# MCU.net
KiCad netlist of a schematic drawn in Altium Designer
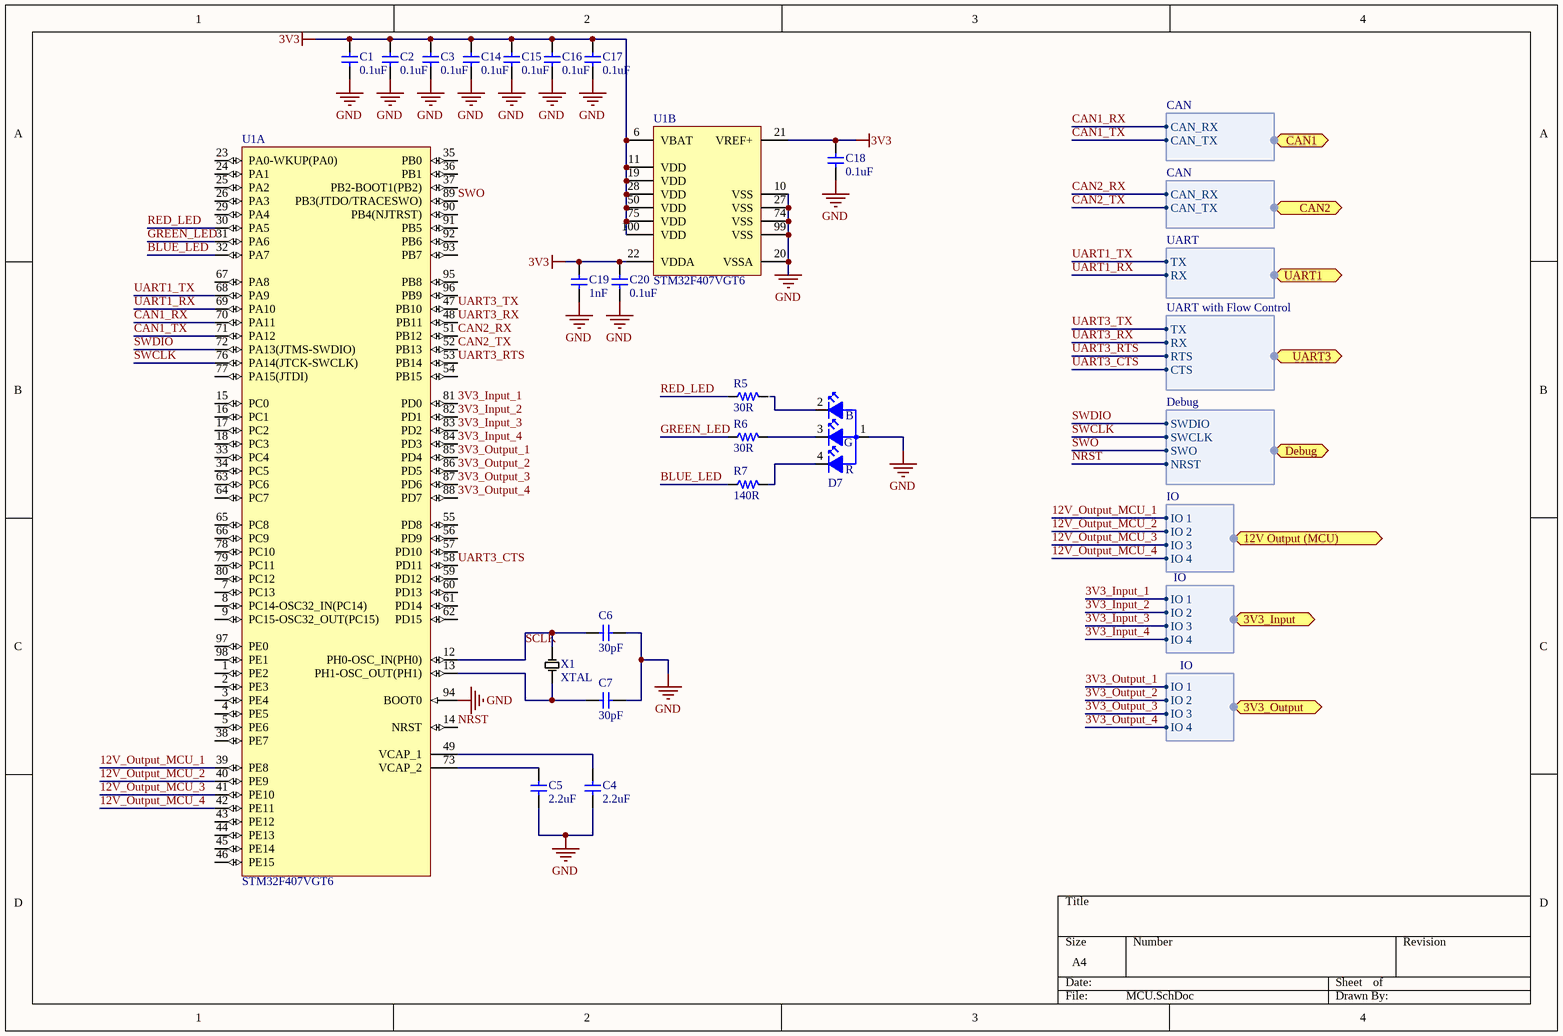
[diagram p0: MCU.SchDoc]

(export (version "E")
  (design (tool "Eeschema 10.0.6"))
  (components
    (comp (ref "C1")
      (value "0.1uF")
      (footprint "PCB_GENERIC_SMD_0603")
      (description "CAP CER 0603 0.1uF 16V X5R 20%")
      (fields (field (name "TOLERANCE") "20%") (field (name "VOLTAGE") "16V"))
      (libsource (lib "CAP-0603") (part "C060-000U1-00"))
    )
    (comp (ref "C2")
      (value "0.1uF")
      (footprint "PCB_GENERIC_SMD_0603")
      (description "CAP CER 0603 0.1uF 16V X5R 20%")
      (fields (field (name "TOLERANCE") "20%") (field (name "VOLTAGE") "16V"))
      (libsource (lib "CAP-0603") (part "C060-000U1-00"))
    )
    (comp (ref "C3")
      (value "0.1uF")
      (footprint "PCB_GENERIC_SMD_0603")
      (description "CAP CER 0603 0.1uF 16V X5R 20%")
      (fields (field (name "TOLERANCE") "20%") (field (name "VOLTAGE") "16V"))
      (libsource (lib "CAP-0603") (part "C060-000U1-00"))
    )
    (comp (ref "C4")
      (value "2.2uF")
      (footprint "PCB_GENERIC_SMD_0603")
      (description "CAP CER 0603 2.2uF 16V X5R 20%")
      (fields (field (name "TOLERANCE") "20%") (field (name "VOLTAGE") "16V"))
      (libsource (lib "CAP-0603") (part "C060-002U2-00"))
    )
    (comp (ref "C5")
      (value "2.2uF")
      (footprint "PCB_GENERIC_SMD_0603")
      (description "CAP CER 0603 2.2uF 16V X5R 20%")
      (fields (field (name "TOLERANCE") "20%") (field (name "VOLTAGE") "16V"))
      (libsource (lib "CAP-0603") (part "C060-002U2-00"))
    )
    (comp (ref "C6")
      (value "30pF")
      (footprint "PCB_GENERIC_SMD_0603")
      (description "CAP CER 0603 30pF 50V NP0 5%")
      (fields (field (name "TOLERANCE") "5%") (field (name "VOLTAGE") "50V"))
      (libsource (lib "CAP-0603") (part "C060-0030P-00"))
    )
    (comp (ref "C7")
      (value "30pF")
      (footprint "PCB_GENERIC_SMD_0603")
      (description "CAP CER 0603 30pF 50V NP0 5%")
      (fields (field (name "TOLERANCE") "5%") (field (name "VOLTAGE") "50V"))
      (libsource (lib "CAP-0603") (part "C060-0030P-00"))
    )
    (comp (ref "C14")
      (value "0.1uF")
      (footprint "PCB_GENERIC_SMD_0603")
      (description "CAP CER 0603 0.1uF 16V X5R 20%")
      (fields (field (name "TOLERANCE") "20%") (field (name "VOLTAGE") "16V"))
      (libsource (lib "CAP-0603") (part "C060-000U1-00"))
    )
    (comp (ref "C15")
      (value "0.1uF")
      (footprint "PCB_GENERIC_SMD_0603")
      (description "CAP CER 0603 0.1uF 16V X5R 20%")
      (fields (field (name "TOLERANCE") "20%") (field (name "VOLTAGE") "16V"))
      (libsource (lib "CAP-0603") (part "C060-000U1-00"))
    )
    (comp (ref "C16")
      (value "0.1uF")
      (footprint "PCB_GENERIC_SMD_0603")
      (description "CAP CER 0603 0.1uF 16V X5R 20%")
      (fields (field (name "TOLERANCE") "20%") (field (name "VOLTAGE") "16V"))
      (libsource (lib "CAP-0603") (part "C060-000U1-00"))
    )
    (comp (ref "C17")
      (value "0.1uF")
      (footprint "PCB_GENERIC_SMD_0603")
      (description "CAP CER 0603 0.1uF 16V X5R 20%")
      (fields (field (name "TOLERANCE") "20%") (field (name "VOLTAGE") "16V"))
      (libsource (lib "CAP-0603") (part "C060-000U1-00"))
    )
    (comp (ref "C18")
      (value "0.1uF")
      (footprint "PCB_GENERIC_SMD_0603")
      (description "CAP CER 0603 0.1uF 16V X5R 20%")
      (fields (field (name "TOLERANCE") "20%") (field (name "VOLTAGE") "16V"))
      (libsource (lib "CAP-0603") (part "C060-000U1-00"))
    )
    (comp (ref "C19")
      (value "1nF")
      (footprint "PCB_GENERIC_SMD_0603")
      (description "CAP CER 0603 1nF 50V X7R 10%")
      (fields (field (name "TOLERANCE") "10%") (field (name "VOLTAGE") "50V"))
      (libsource (lib "CAP-0603") (part "C060-0001N-00"))
    )
    (comp (ref "C20")
      (value "0.1uF")
      (footprint "PCB_GENERIC_SMD_0603")
      (description "CAP CER 0603 0.1uF 16V X5R 20%")
      (fields (field (name "TOLERANCE") "20%") (field (name "VOLTAGE") "16V"))
      (libsource (lib "CAP-0603") (part "C060-000U1-00"))
    )
    (comp (ref "D7")
      (value "D0S4-000CR-00")
      (footprint "CLMVB-FKA")
      (description "LED 4SMD RGB 2Vf 3Vf 3Vf 20mA 10mA 10mA")
      (libsource (lib "LED-4SMD") (part "D0S4-000CR-00"))
    )
    (comp (ref "R5")
      (value "30R")
      (footprint "PCB_GENERIC_SMD_0603")
      (description "RES 0603 30ohm 5% 100mW")
      (fields (field (name "TOLERANCE") "5%") (field (name "POWER") "100mW"))
      (libsource (lib "RES-0603") (part "R060-00300-05"))
    )
    (comp (ref "R6")
      (value "30R")
      (footprint "PCB_GENERIC_SMD_0603")
      (description "RES 0603 30ohm 5% 100mW")
      (fields (field (name "TOLERANCE") "5%") (field (name "POWER") "100mW"))
      (libsource (lib "RES-0603") (part "R060-00300-05"))
    )
    (comp (ref "R7")
      (value "140R")
      (footprint "PCB_GENERIC_SMD_0603")
      (description "RES 0603 140ohm 5% 63mW")
      (fields (field (name "TOLERANCE") "5%") (field (name "POWER") "63mW"))
      (libsource (lib "RES-0603") (part "R060-00141-05"))
    )
    (comp (ref "U1")
      (value "STM32F407VGT6")
      (footprint "STM-LQFP100_M")
      (fields (field (name "MANUFACTURER") "STMicroelectronics"))
      (libsource (lib "STMicroelectronics STM32 F4") (part "STM32F407VGT6"))
    )
    (comp (ref "X1") (value "XTAL") (footprint "CRYSTAL_8MHZ") (libsource (lib "Crystal") (part "Crystal")))
  )
  (nets
    (net (code "8") (name "/3V3_Input_1") (class "Default")
      (node (ref "U1") (pin "81") (pinfunction "PD0_81") (pintype "bidirectional"))
    )
    (net (code "9") (name "/3V3_Input_2") (class "Default")
      (node (ref "U1") (pin "82") (pinfunction "PD1_82") (pintype "bidirectional"))
    )
    (net (code "10") (name "/3V3_Input_3") (class "Default")
      (node (ref "U1") (pin "83") (pinfunction "PD2_83") (pintype "bidirectional"))
    )
    (net (code "11") (name "/3V3_Input_4") (class "Default")
      (node (ref "U1") (pin "84") (pinfunction "PD3_84") (pintype "bidirectional"))
    )
    (net (code "12") (name "/3V3_Output_1") (class "Default")
      (node (ref "U1") (pin "85") (pinfunction "PD4_85") (pintype "bidirectional"))
    )
    (net (code "13") (name "/3V3_Output_2") (class "Default")
      (node (ref "U1") (pin "86") (pinfunction "PD5_86") (pintype "bidirectional"))
    )
    (net (code "14") (name "/3V3_Output_3") (class "Default")
      (node (ref "U1") (pin "87") (pinfunction "PD6_87") (pintype "bidirectional"))
    )
    (net (code "15") (name "/3V3_Output_4") (class "Default")
      (node (ref "U1") (pin "88") (pinfunction "PD7_88") (pintype "bidirectional"))
    )
    (net (code "16") (name "/12V_Output_MCU_1") (class "Default")
      (node (ref "U1") (pin "39") (pinfunction "PE8_39") (pintype "bidirectional"))
    )
    (net (code "17") (name "/12V_Output_MCU_2") (class "Default")
      (node (ref "U1") (pin "40") (pinfunction "PE9_40") (pintype "bidirectional"))
    )
    (net (code "18") (name "/12V_Output_MCU_3") (class "Default")
      (node (ref "U1") (pin "41") (pinfunction "PE10_41") (pintype "bidirectional"))
    )
    (net (code "19") (name "/12V_Output_MCU_4") (class "Default")
      (node (ref "U1") (pin "42") (pinfunction "PE11_42") (pintype "bidirectional"))
    )
    (net (code "20") (name "/BLUE_LED") (class "Default")
      (node (ref "R7") (pin "1") (pinfunction "1_1") (pintype "passive"))
      (node (ref "U1") (pin "32") (pinfunction "PA7_32") (pintype "bidirectional"))
    )
    (net (code "21") (name "/CAN1_RX") (class "Default")
      (node (ref "U1") (pin "70") (pinfunction "PA11_70") (pintype "bidirectional"))
    )
    (net (code "22") (name "/CAN1_TX") (class "Default")
      (node (ref "U1") (pin "71") (pinfunction "PA12_71") (pintype "bidirectional"))
    )
    (net (code "23") (name "/CAN2_RX") (class "Default")
      (node (ref "U1") (pin "51") (pinfunction "PB12_51") (pintype "bidirectional"))
    )
    (net (code "24") (name "/CAN2_TX") (class "Default")
      (node (ref "U1") (pin "52") (pinfunction "PB13_52") (pintype "bidirectional"))
    )
    (net (code "25") (name "/GREEN_LED") (class "Default")
      (node (ref "R6") (pin "1") (pinfunction "1_1") (pintype "passive"))
      (node (ref "U1") (pin "31") (pinfunction "PA6_31") (pintype "bidirectional"))
    )
    (net (code "26") (name "/NRST") (class "Default")
      (node (ref "U1") (pin "14") (pinfunction "NRST_14") (pintype "bidirectional"))
    )
    (net (code "27") (name "/RED_LED") (class "Default")
      (node (ref "R5") (pin "1") (pinfunction "1_1") (pintype "passive"))
      (node (ref "U1") (pin "30") (pinfunction "PA5_30") (pintype "bidirectional"))
    )
    (net (code "28") (name "/SCLK") (class "Default")
      (node (ref "C6") (pin "1") (pinfunction "1_1") (pintype "passive"))
      (node (ref "U1") (pin "12") (pinfunction "PH0-OSC_IN(PH0)_12") (pintype "bidirectional"))
      (node (ref "X1") (pin "1") (pintype "passive"))
    )
    (net (code "29") (name "/SWCLK") (class "Default")
      (node (ref "U1") (pin "76") (pinfunction "PA14(JTCK-SWCLK)_76") (pintype "bidirectional"))
    )
    (net (code "30") (name "/SWDIO") (class "Default")
      (node (ref "U1") (pin "72") (pinfunction "PA13(JTMS-SWDIO)_72") (pintype "bidirectional"))
    )
    (net (code "31") (name "/SWO") (class "Default")
      (node (ref "U1") (pin "89") (pinfunction "PB3(JTDO/TRACESWO)_89") (pintype "bidirectional"))
    )
    (net (code "32") (name "/UART1_RX") (class "Default")
      (node (ref "U1") (pin "69") (pinfunction "PA10_69") (pintype "bidirectional"))
    )
    (net (code "33") (name "/UART1_TX") (class "Default")
      (node (ref "U1") (pin "68") (pinfunction "PA9_68") (pintype "bidirectional"))
    )
    (net (code "34") (name "/UART3_CTS") (class "Default")
      (node (ref "U1") (pin "58") (pinfunction "PD11_58") (pintype "bidirectional"))
    )
    (net (code "35") (name "/UART3_RTS") (class "Default")
      (node (ref "U1") (pin "53") (pinfunction "PB14_53") (pintype "bidirectional"))
    )
    (net (code "36") (name "/UART3_RX") (class "Default")
      (node (ref "U1") (pin "48") (pinfunction "PB11_48") (pintype "bidirectional"))
    )
    (net (code "37") (name "/UART3_TX") (class "Default")
      (node (ref "U1") (pin "47") (pinfunction "PB10_47") (pintype "bidirectional"))
    )
    (net (code "43") (name "3V3") (class "Default")
      (node (ref "C1") (pin "2") (pinfunction "2_2") (pintype "passive"))
      (node (ref "C14") (pin "2") (pinfunction "2_2") (pintype "passive"))
      (node (ref "C15") (pin "2") (pinfunction "2_2") (pintype "passive"))
      (node (ref "C16") (pin "2") (pinfunction "2_2") (pintype "passive"))
      (node (ref "C17") (pin "2") (pinfunction "2_2") (pintype "passive"))
      (node (ref "C18") (pin "2") (pinfunction "2_2") (pintype "passive"))
      (node (ref "C19") (pin "2") (pinfunction "2_2") (pintype "passive"))
      (node (ref "C2") (pin "2") (pinfunction "2_2") (pintype "passive"))
      (node (ref "C20") (pin "2") (pinfunction "2_2") (pintype "passive"))
      (node (ref "C3") (pin "2") (pinfunction "2_2") (pintype "passive"))
      (node (ref "U1") (pin "100") (pinfunction "VDD_100") (pintype "power_in"))
      (node (ref "U1") (pin "11") (pinfunction "VDD_11") (pintype "power_in"))
      (node (ref "U1") (pin "19") (pinfunction "VDD_19") (pintype "power_in"))
      (node (ref "U1") (pin "21") (pinfunction "VREF+_21") (pintype "power_in"))
      (node (ref "U1") (pin "22") (pinfunction "VDDA_22") (pintype "power_in"))
      (node (ref "U1") (pin "28") (pinfunction "VDD_28") (pintype "power_in"))
      (node (ref "U1") (pin "50") (pinfunction "VDD_50") (pintype "power_in"))
      (node (ref "U1") (pin "6") (pinfunction "VBAT_6") (pintype "power_in"))
      (node (ref "U1") (pin "75") (pinfunction "VDD_75") (pintype "power_in"))
    )
    (net (code "44") (name "GND") (class "Default")
      (node (ref "C1") (pin "1") (pinfunction "1_1") (pintype "passive"))
      (node (ref "C14") (pin "1") (pinfunction "1_1") (pintype "passive"))
      (node (ref "C15") (pin "1") (pinfunction "1_1") (pintype "passive"))
      (node (ref "C16") (pin "1") (pinfunction "1_1") (pintype "passive"))
      (node (ref "C17") (pin "1") (pinfunction "1_1") (pintype "passive"))
      (node (ref "C18") (pin "1") (pinfunction "1_1") (pintype "passive"))
      (node (ref "C19") (pin "1") (pinfunction "1_1") (pintype "passive"))
      (node (ref "C2") (pin "1") (pinfunction "1_1") (pintype "passive"))
      (node (ref "C20") (pin "1") (pinfunction "1_1") (pintype "passive"))
      (node (ref "C3") (pin "1") (pinfunction "1_1") (pintype "passive"))
      (node (ref "C4") (pin "1") (pinfunction "1_1") (pintype "passive"))
      (node (ref "C5") (pin "1") (pinfunction "1_1") (pintype "passive"))
      (node (ref "C6") (pin "2") (pinfunction "2_2") (pintype "passive"))
      (node (ref "C7") (pin "2") (pinfunction "2_2") (pintype "passive"))
      (node (ref "D7") (pin "1") (pinfunction "Red_1") (pintype "passive"))
      (node (ref "U1") (pin "10") (pinfunction "VSS_10") (pintype "power_in"))
      (node (ref "U1") (pin "20") (pinfunction "VSSA_20") (pintype "power_in"))
      (node (ref "U1") (pin "27") (pinfunction "VSS_27") (pintype "power_in"))
      (node (ref "U1") (pin "74") (pinfunction "VSS_74") (pintype "power_in"))
      (node (ref "U1") (pin "94") (pinfunction "BOOT0_94") (pintype "input"))
      (node (ref "U1") (pin "99") (pinfunction "VSS_99") (pintype "power_in"))
    )
    (net (code "45") (name "Net-(D7-Blue)") (class "Default")
      (node (ref "D7") (pin "3") (pinfunction "Blue_3") (pintype "passive"))
      (node (ref "R6") (pin "2") (pinfunction "2_2") (pintype "passive"))
    )
    (net (code "46") (name "Net-(D7-Pad4)") (class "Default")
      (node (ref "D7") (pin "4") (pinfunction "4_4") (pintype "passive"))
      (node (ref "R7") (pin "2") (pinfunction "2_2") (pintype "passive"))
    )
    (net (code "47") (name "Net-(U1A-PH1-OSC_OUT(PH1))") (class "Default")
      (node (ref "C7") (pin "1") (pinfunction "1_1") (pintype "passive"))
      (node (ref "U1") (pin "13") (pinfunction "PH1-OSC_OUT(PH1)_13") (pintype "bidirectional"))
      (node (ref "X1") (pin "2") (pintype "passive"))
    )
    (net (code "48") (name "Net-(U1A-VCAP_1)") (class "Default")
      (node (ref "C4") (pin "2") (pinfunction "2_2") (pintype "passive"))
      (node (ref "U1") (pin "49") (pinfunction "VCAP_1_49") (pintype "power_in"))
    )
    (net (code "49") (name "Net-(U1A-VCAP_2)") (class "Default")
      (node (ref "C5") (pin "2") (pinfunction "2_2") (pintype "passive"))
      (node (ref "U1") (pin "73") (pinfunction "VCAP_2_73") (pintype "power_in"))
    )
    (net (code "50") (name "unconnected-(D7-Green-Pad2)") (class "Default")
      (node (ref "D7") (pin "2") (pinfunction "Green_2") (pintype "passive"))
    )
    (net (code "51") (name "unconnected-(R5-Pad2)") (class "Default")
      (node (ref "R5") (pin "2") (pinfunction "2_2") (pintype "passive"))
    )
    (net (code "52") (name "unconnected-(U1A-PA0-WKUP(PA0)-Pad23)") (class "Default")
      (node (ref "U1") (pin "23") (pinfunction "PA0-WKUP(PA0)_23") (pintype "bidirectional"))
    )
    (net (code "53") (name "unconnected-(U1A-PA1-Pad24)") (class "Default")
      (node (ref "U1") (pin "24") (pinfunction "PA1_24") (pintype "bidirectional"))
    )
    (net (code "54") (name "unconnected-(U1A-PA2-Pad25)") (class "Default")
      (node (ref "U1") (pin "25") (pinfunction "PA2_25") (pintype "bidirectional"))
    )
    (net (code "55") (name "unconnected-(U1A-PA3-Pad26)") (class "Default")
      (node (ref "U1") (pin "26") (pinfunction "PA3_26") (pintype "bidirectional"))
    )
    (net (code "56") (name "unconnected-(U1A-PA4-Pad29)") (class "Default")
      (node (ref "U1") (pin "29") (pinfunction "PA4_29") (pintype "bidirectional"))
    )
    (net (code "57") (name "unconnected-(U1A-PA8-Pad67)") (class "Default")
      (node (ref "U1") (pin "67") (pinfunction "PA8_67") (pintype "bidirectional"))
    )
    (net (code "58") (name "unconnected-(U1A-PA15(JTDI)-Pad77)") (class "Default")
      (node (ref "U1") (pin "77") (pinfunction "PA15(JTDI)_77") (pintype "bidirectional"))
    )
    (net (code "59") (name "unconnected-(U1A-PB0-Pad35)") (class "Default")
      (node (ref "U1") (pin "35") (pinfunction "PB0_35") (pintype "bidirectional"))
    )
    (net (code "60") (name "unconnected-(U1A-PB1-Pad36)") (class "Default")
      (node (ref "U1") (pin "36") (pinfunction "PB1_36") (pintype "bidirectional"))
    )
    (net (code "61") (name "unconnected-(U1A-PB2-BOOT1(PB2)-Pad37)") (class "Default")
      (node (ref "U1") (pin "37") (pinfunction "PB2-BOOT1(PB2)_37") (pintype "bidirectional"))
    )
    (net (code "62") (name "unconnected-(U1A-PB4(NJTRST)-Pad90)") (class "Default")
      (node (ref "U1") (pin "90") (pinfunction "PB4(NJTRST)_90") (pintype "bidirectional"))
    )
    (net (code "63") (name "unconnected-(U1A-PB5-Pad91)") (class "Default")
      (node (ref "U1") (pin "91") (pinfunction "PB5_91") (pintype "bidirectional"))
    )
    (net (code "64") (name "unconnected-(U1A-PB6-Pad92)") (class "Default")
      (node (ref "U1") (pin "92") (pinfunction "PB6_92") (pintype "bidirectional"))
    )
    (net (code "65") (name "unconnected-(U1A-PB7-Pad93)") (class "Default")
      (node (ref "U1") (pin "93") (pinfunction "PB7_93") (pintype "bidirectional"))
    )
    (net (code "66") (name "unconnected-(U1A-PB8-Pad95)") (class "Default")
      (node (ref "U1") (pin "95") (pinfunction "PB8_95") (pintype "bidirectional"))
    )
    (net (code "67") (name "unconnected-(U1A-PB9-Pad96)") (class "Default")
      (node (ref "U1") (pin "96") (pinfunction "PB9_96") (pintype "bidirectional"))
    )
    (net (code "68") (name "unconnected-(U1A-PB15-Pad54)") (class "Default")
      (node (ref "U1") (pin "54") (pinfunction "PB15_54") (pintype "bidirectional"))
    )
    (net (code "69") (name "unconnected-(U1A-PC0-Pad15)") (class "Default")
      (node (ref "U1") (pin "15") (pinfunction "PC0_15") (pintype "bidirectional"))
    )
    (net (code "70") (name "unconnected-(U1A-PC1-Pad16)") (class "Default")
      (node (ref "U1") (pin "16") (pinfunction "PC1_16") (pintype "bidirectional"))
    )
    (net (code "71") (name "unconnected-(U1A-PC2-Pad17)") (class "Default")
      (node (ref "U1") (pin "17") (pinfunction "PC2_17") (pintype "bidirectional"))
    )
    (net (code "72") (name "unconnected-(U1A-PC3-Pad18)") (class "Default")
      (node (ref "U1") (pin "18") (pinfunction "PC3_18") (pintype "bidirectional"))
    )
    (net (code "73") (name "unconnected-(U1A-PC4-Pad33)") (class "Default")
      (node (ref "U1") (pin "33") (pinfunction "PC4_33") (pintype "bidirectional"))
    )
    (net (code "74") (name "unconnected-(U1A-PC5-Pad34)") (class "Default")
      (node (ref "U1") (pin "34") (pinfunction "PC5_34") (pintype "bidirectional"))
    )
    (net (code "75") (name "unconnected-(U1A-PC6-Pad63)") (class "Default")
      (node (ref "U1") (pin "63") (pinfunction "PC6_63") (pintype "bidirectional"))
    )
    (net (code "76") (name "unconnected-(U1A-PC7-Pad64)") (class "Default")
      (node (ref "U1") (pin "64") (pinfunction "PC7_64") (pintype "bidirectional"))
    )
    (net (code "77") (name "unconnected-(U1A-PC8-Pad65)") (class "Default")
      (node (ref "U1") (pin "65") (pinfunction "PC8_65") (pintype "bidirectional"))
    )
    (net (code "78") (name "unconnected-(U1A-PC9-Pad66)") (class "Default")
      (node (ref "U1") (pin "66") (pinfunction "PC9_66") (pintype "bidirectional"))
    )
    (net (code "79") (name "unconnected-(U1A-PC10-Pad78)") (class "Default")
      (node (ref "U1") (pin "78") (pinfunction "PC10_78") (pintype "bidirectional"))
    )
    (net (code "80") (name "unconnected-(U1A-PC11-Pad79)") (class "Default")
      (node (ref "U1") (pin "79") (pinfunction "PC11_79") (pintype "bidirectional"))
    )
    (net (code "81") (name "unconnected-(U1A-PC12-Pad80)") (class "Default")
      (node (ref "U1") (pin "80") (pinfunction "PC12_80") (pintype "bidirectional"))
    )
    (net (code "82") (name "unconnected-(U1A-PC13-Pad7)") (class "Default")
      (node (ref "U1") (pin "7") (pinfunction "PC13_7") (pintype "bidirectional"))
    )
    (net (code "83") (name "unconnected-(U1A-PC14-OSC32_IN(PC14)-Pad8)") (class "Default")
      (node (ref "U1") (pin "8") (pinfunction "PC14-OSC32_IN(PC14)_8") (pintype "bidirectional"))
    )
    (net (code "84") (name "unconnected-(U1A-PC15-OSC32_OUT(PC15)-Pad9)") (class "Default")
      (node (ref "U1") (pin "9") (pinfunction "PC15-OSC32_OUT(PC15)_9") (pintype "bidirectional"))
    )
    (net (code "85") (name "unconnected-(U1A-PD8-Pad55)") (class "Default")
      (node (ref "U1") (pin "55") (pinfunction "PD8_55") (pintype "bidirectional"))
    )
    (net (code "86") (name "unconnected-(U1A-PD9-Pad56)") (class "Default")
      (node (ref "U1") (pin "56") (pinfunction "PD9_56") (pintype "bidirectional"))
    )
    (net (code "87") (name "unconnected-(U1A-PD10-Pad57)") (class "Default")
      (node (ref "U1") (pin "57") (pinfunction "PD10_57") (pintype "bidirectional"))
    )
    (net (code "88") (name "unconnected-(U1A-PD12-Pad59)") (class "Default")
      (node (ref "U1") (pin "59") (pinfunction "PD12_59") (pintype "bidirectional"))
    )
    (net (code "89") (name "unconnected-(U1A-PD13-Pad60)") (class "Default")
      (node (ref "U1") (pin "60") (pinfunction "PD13_60") (pintype "bidirectional"))
    )
    (net (code "90") (name "unconnected-(U1A-PD14-Pad61)") (class "Default")
      (node (ref "U1") (pin "61") (pinfunction "PD14_61") (pintype "bidirectional"))
    )
    (net (code "91") (name "unconnected-(U1A-PD15-Pad62)") (class "Default")
      (node (ref "U1") (pin "62") (pinfunction "PD15_62") (pintype "bidirectional"))
    )
    (net (code "92") (name "unconnected-(U1A-PE0-Pad97)") (class "Default")
      (node (ref "U1") (pin "97") (pinfunction "PE0_97") (pintype "bidirectional"))
    )
    (net (code "93") (name "unconnected-(U1A-PE1-Pad98)") (class "Default")
      (node (ref "U1") (pin "98") (pinfunction "PE1_98") (pintype "bidirectional"))
    )
    (net (code "94") (name "unconnected-(U1A-PE2-Pad1)") (class "Default")
      (node (ref "U1") (pin "1") (pinfunction "PE2_1") (pintype "bidirectional"))
    )
    (net (code "95") (name "unconnected-(U1A-PE3-Pad2)") (class "Default")
      (node (ref "U1") (pin "2") (pinfunction "PE3_2") (pintype "bidirectional"))
    )
    (net (code "96") (name "unconnected-(U1A-PE4-Pad3)") (class "Default")
      (node (ref "U1") (pin "3") (pinfunction "PE4_3") (pintype "bidirectional"))
    )
    (net (code "97") (name "unconnected-(U1A-PE5-Pad4)") (class "Default")
      (node (ref "U1") (pin "4") (pinfunction "PE5_4") (pintype "bidirectional"))
    )
    (net (code "98") (name "unconnected-(U1A-PE6-Pad5)") (class "Default")
      (node (ref "U1") (pin "5") (pinfunction "PE6_5") (pintype "bidirectional"))
    )
    (net (code "99") (name "unconnected-(U1A-PE7-Pad38)") (class "Default")
      (node (ref "U1") (pin "38") (pinfunction "PE7_38") (pintype "bidirectional"))
    )
    (net (code "100") (name "unconnected-(U1A-PE12-Pad43)") (class "Default")
      (node (ref "U1") (pin "43") (pinfunction "PE12_43") (pintype "bidirectional"))
    )
    (net (code "101") (name "unconnected-(U1A-PE13-Pad44)") (class "Default")
      (node (ref "U1") (pin "44") (pinfunction "PE13_44") (pintype "bidirectional"))
    )
    (net (code "102") (name "unconnected-(U1A-PE14-Pad45)") (class "Default")
      (node (ref "U1") (pin "45") (pinfunction "PE14_45") (pintype "bidirectional"))
    )
    (net (code "103") (name "unconnected-(U1A-PE15-Pad46)") (class "Default")
      (node (ref "U1") (pin "46") (pinfunction "PE15_46") (pintype "bidirectional"))
    )
  )
)
